# Force.net
KiCad netlist of a schematic drawn in Altium Designer
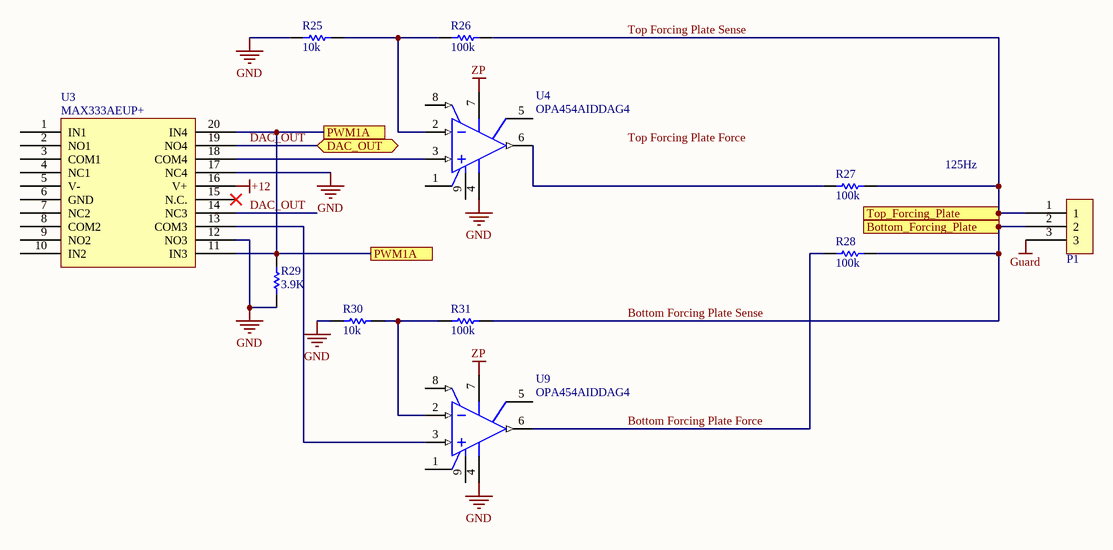
[diagram p0: Force.SchDoc]

(export (version "E")
  (design (tool "Eeschema 10.0.6"))
  (components
    (comp (ref "P1")
      (value "Triax_Conn")
      (footprint "Triax_Conn")
      (libsource (lib "ZLS_Schematic_lib") (part "Triax_Conn"))
    )
    (comp (ref "R25")
      (value "10k")
      (footprint "RESC0402(1005)_M")
      (libsource (lib "Altium Content Vault") (part "CMP-1011-00463-1"))
    )
    (comp (ref "R26")
      (value "100k")
      (footprint "RESC0402(1005)_M")
      (libsource (lib "Altium Content Vault") (part "CMP-1011-00463-1"))
    )
    (comp (ref "R27")
      (value "100k")
      (footprint "RESC0402(1005)_M")
      (libsource (lib "Altium Content Vault") (part "CMP-1011-00651-1"))
    )
    (comp (ref "R28")
      (value "100k")
      (footprint "RESC0402(1005)_M")
      (libsource (lib "Altium Content Vault") (part "CMP-1011-00651-1"))
    )
    (comp (ref "R29")
      (value "3.9K")
      (footprint "RESC0402(1005)_M")
      (libsource (lib "Altium Content Vault") (part "CMP-1011-00463-1"))
    )
    (comp (ref "R30")
      (value "10k")
      (footprint "RESC0402(1005)_M")
      (libsource (lib "Altium Content Vault") (part "CMP-1011-00463-1"))
    )
    (comp (ref "R31")
      (value "100k")
      (footprint "RESC0402(1005)_M")
      (libsource (lib "Altium Content Vault") (part "CMP-1011-00463-1"))
    )
    (comp (ref "U3")
      (value "MAX333AEUP+")
      (footprint "TSOP65P640X90-20N")
      (description "IC SWITCH QUAD SPDT 20TSSOP")
      (fields (field (name "MANUFACTURER") "Maxim Integrated") (field (name "BASE PART NUMBER") "MAX333"))
      (libsource (lib "ZLS_Schematic_lib") (part "MAX333CWP+"))
    )
    (comp (ref "U4")
      (value "OPA454AIDDAG4")
      (footprint "TI-DDA8-2745X2245TP_N")
      (fields (field (name "MANUFACTURER") "Texas Instruments"))
      (libsource (lib "Altium Content Vault") (part "TI-OPA454-DDA8"))
    )
    (comp (ref "U9")
      (value "OPA454AIDDAG4")
      (footprint "TI-DDA8-2745X2245TP_N")
      (fields (field (name "MANUFACTURER") "Texas Instruments"))
      (libsource (lib "Altium Content Vault") (part "TI-OPA454-DDA8"))
    )
  )
  (nets
    (net (code "1") (name "+12") (class "Default")
      (node (ref "U3") (pin "16") (pinfunction "V+_16") (pintype "power_in"))
    )
    (net (code "2") (name "/Bottom Forcing Plate Force") (class "Default")
      (node (ref "R28") (pin "2") (pinfunction "2_2") (pintype "passive"))
      (node (ref "U9") (pin "6") (pinfunction "OUT_6") (pintype "output"))
    )
    (net (code "3") (name "/Bottom Forcing Plate Sense") (class "Default")
      (node (ref "P1") (pin "2") (pinfunction "2_2") (pintype "passive"))
      (node (ref "R28") (pin "1") (pinfunction "1_1") (pintype "passive"))
      (node (ref "R31") (pin "2") (pinfunction "2_2") (pintype "passive"))
    )
    (net (code "4") (name "/DAC_OUT") (class "Default")
      (node (ref "U3") (pin "14") (pinfunction "NC3_14") (pintype "passive"))
      (node (ref "U3") (pin "19") (pinfunction "NO4_19") (pintype "passive"))
    )
    (net (code "5") (name "/PWM1A") (class "Default")
      (node (ref "R29") (pin "2") (pinfunction "2_2") (pintype "passive"))
      (node (ref "U3") (pin "11") (pinfunction "IN3_11") (pintype "passive"))
      (node (ref "U3") (pin "20") (pinfunction "IN4_20") (pintype "passive"))
    )
    (net (code "7") (name "/Top Forcing Plate Sense") (class "Default")
      (node (ref "P1") (pin "1") (pinfunction "1_1") (pintype "passive"))
      (node (ref "R26") (pin "2") (pinfunction "2_2") (pintype "passive"))
      (node (ref "R27") (pin "1") (pinfunction "1_1") (pintype "passive"))
    )
    (net (code "8") (name "GND") (class "Default")
      (node (ref "R25") (pin "1") (pinfunction "1_1") (pintype "passive"))
      (node (ref "R29") (pin "1") (pinfunction "1_1") (pintype "passive"))
      (node (ref "R30") (pin "1") (pinfunction "1_1") (pintype "passive"))
      (node (ref "U3") (pin "12") (pinfunction "NO3_12") (pintype "passive"))
      (node (ref "U3") (pin "17") (pinfunction "NC4_17") (pintype "passive"))
      (node (ref "U4") (pin "4") (pinfunction "V-_4") (pintype "power_in"))
      (node (ref "U9") (pin "4") (pinfunction "V-_4") (pintype "power_in"))
    )
    (net (code "9") (name "Guard") (class "Default")
      (node (ref "P1") (pin "3") (pinfunction "3_3") (pintype "passive"))
    )
    (net (code "10") (name "Net-(U3-COM3)") (class "Default")
      (node (ref "U3") (pin "13") (pinfunction "COM3_13") (pintype "passive"))
      (node (ref "U9") (pin "3") (pinfunction "IN+_3") (pintype "input"))
    )
    (net (code "11") (name "Net-(U3-COM4)") (class "Default")
      (node (ref "U3") (pin "18") (pinfunction "COM4_18") (pintype "passive"))
      (node (ref "U4") (pin "3") (pinfunction "IN+_3") (pintype "input"))
    )
    (net (code "12") (name "Net-(U4-IN-)") (class "Default")
      (node (ref "R25") (pin "2") (pinfunction "2_2") (pintype "passive"))
      (node (ref "R26") (pin "1") (pinfunction "1_1") (pintype "passive"))
      (node (ref "U4") (pin "2") (pinfunction "IN-_2") (pintype "input"))
    )
    (net (code "13") (name "Net-(U4-OUT)") (class "Default")
      (node (ref "R27") (pin "2") (pinfunction "2_2") (pintype "passive"))
      (node (ref "U4") (pin "6") (pinfunction "OUT_6") (pintype "output"))
    )
    (net (code "14") (name "Net-(U9-IN-)") (class "Default")
      (node (ref "R30") (pin "2") (pinfunction "2_2") (pintype "passive"))
      (node (ref "R31") (pin "1") (pinfunction "1_1") (pintype "passive"))
      (node (ref "U9") (pin "2") (pinfunction "IN-_2") (pintype "input"))
    )
    (net (code "15") (name "ZP") (class "Default")
      (node (ref "U4") (pin "7") (pinfunction "V+_7") (pintype "power_in"))
      (node (ref "U9") (pin "7") (pinfunction "V+_7") (pintype "power_in"))
    )
    (net (code "16") (name "unconnected-(U3-COM1-Pad3)") (class "Default")
      (node (ref "U3") (pin "3") (pinfunction "COM1_3") (pintype "passive"))
    )
    (net (code "17") (name "unconnected-(U3-COM2-Pad8)") (class "Default")
      (node (ref "U3") (pin "8") (pinfunction "COM2_8") (pintype "passive"))
    )
    (net (code "18") (name "unconnected-(U3-GND-Pad6)") (class "Default")
      (node (ref "U3") (pin "6") (pinfunction "GND_6") (pintype "passive"))
    )
    (net (code "19") (name "unconnected-(U3-IN1-Pad1)") (class "Default")
      (node (ref "U3") (pin "1") (pinfunction "IN1_1") (pintype "passive"))
    )
    (net (code "20") (name "unconnected-(U3-IN2-Pad10)") (class "Default")
      (node (ref "U3") (pin "10") (pinfunction "IN2_10") (pintype "passive"))
    )
    (net (code "21") (name "unconnected-(U3-N.C.-Pad15)") (class "Default")
      (node (ref "U3") (pin "15") (pinfunction "N.C._15") (pintype "passive+no_connect"))
    )
    (net (code "22") (name "unconnected-(U3-NC1-Pad4)") (class "Default")
      (node (ref "U3") (pin "4") (pinfunction "NC1_4") (pintype "passive"))
    )
    (net (code "23") (name "unconnected-(U3-NC2-Pad7)") (class "Default")
      (node (ref "U3") (pin "7") (pinfunction "NC2_7") (pintype "passive"))
    )
    (net (code "24") (name "unconnected-(U3-NO1-Pad2)") (class "Default")
      (node (ref "U3") (pin "2") (pinfunction "NO1_2") (pintype "passive"))
    )
    (net (code "25") (name "unconnected-(U3-NO2-Pad9)") (class "Default")
      (node (ref "U3") (pin "9") (pinfunction "NO2_9") (pintype "passive"))
    )
    (net (code "26") (name "unconnected-(U3-V--Pad5)") (class "Default")
      (node (ref "U3") (pin "5") (pinfunction "V-_5") (pintype "power_in"))
    )
    (net (code "27") (name "unconnected-(U4-EP-Pad9)") (class "Default")
      (node (ref "U4") (pin "9") (pinfunction "EP_9") (pintype "power_in"))
    )
    (net (code "28") (name "unconnected-(U4-E{slash}D-Pad8)") (class "Default")
      (node (ref "U4") (pin "8") (pinfunction "E/D_8") (pintype "input"))
    )
    (net (code "29") (name "unconnected-(U4-E{slash}D_COM-Pad1)") (class "Default")
      (node (ref "U4") (pin "1") (pinfunction "E/D_COM_1") (pintype "power_in"))
    )
    (net (code "30") (name "unconnected-(U4-STATUS_FLAG-Pad5)") (class "Default")
      (node (ref "U4") (pin "5") (pinfunction "STATUS_FLAG_5") (pintype "open_collector"))
    )
    (net (code "31") (name "unconnected-(U9-EP-Pad9)") (class "Default")
      (node (ref "U9") (pin "9") (pinfunction "EP_9") (pintype "power_in"))
    )
    (net (code "32") (name "unconnected-(U9-E{slash}D-Pad8)") (class "Default")
      (node (ref "U9") (pin "8") (pinfunction "E/D_8") (pintype "input"))
    )
    (net (code "33") (name "unconnected-(U9-E{slash}D_COM-Pad1)") (class "Default")
      (node (ref "U9") (pin "1") (pinfunction "E/D_COM_1") (pintype "power_in"))
    )
    (net (code "34") (name "unconnected-(U9-STATUS_FLAG-Pad5)") (class "Default")
      (node (ref "U9") (pin "5") (pinfunction "STATUS_FLAG_5") (pintype "open_collector"))
    )
  )
)
